# shield.net
KiCad netlist of a schematic drawn in EAGLE
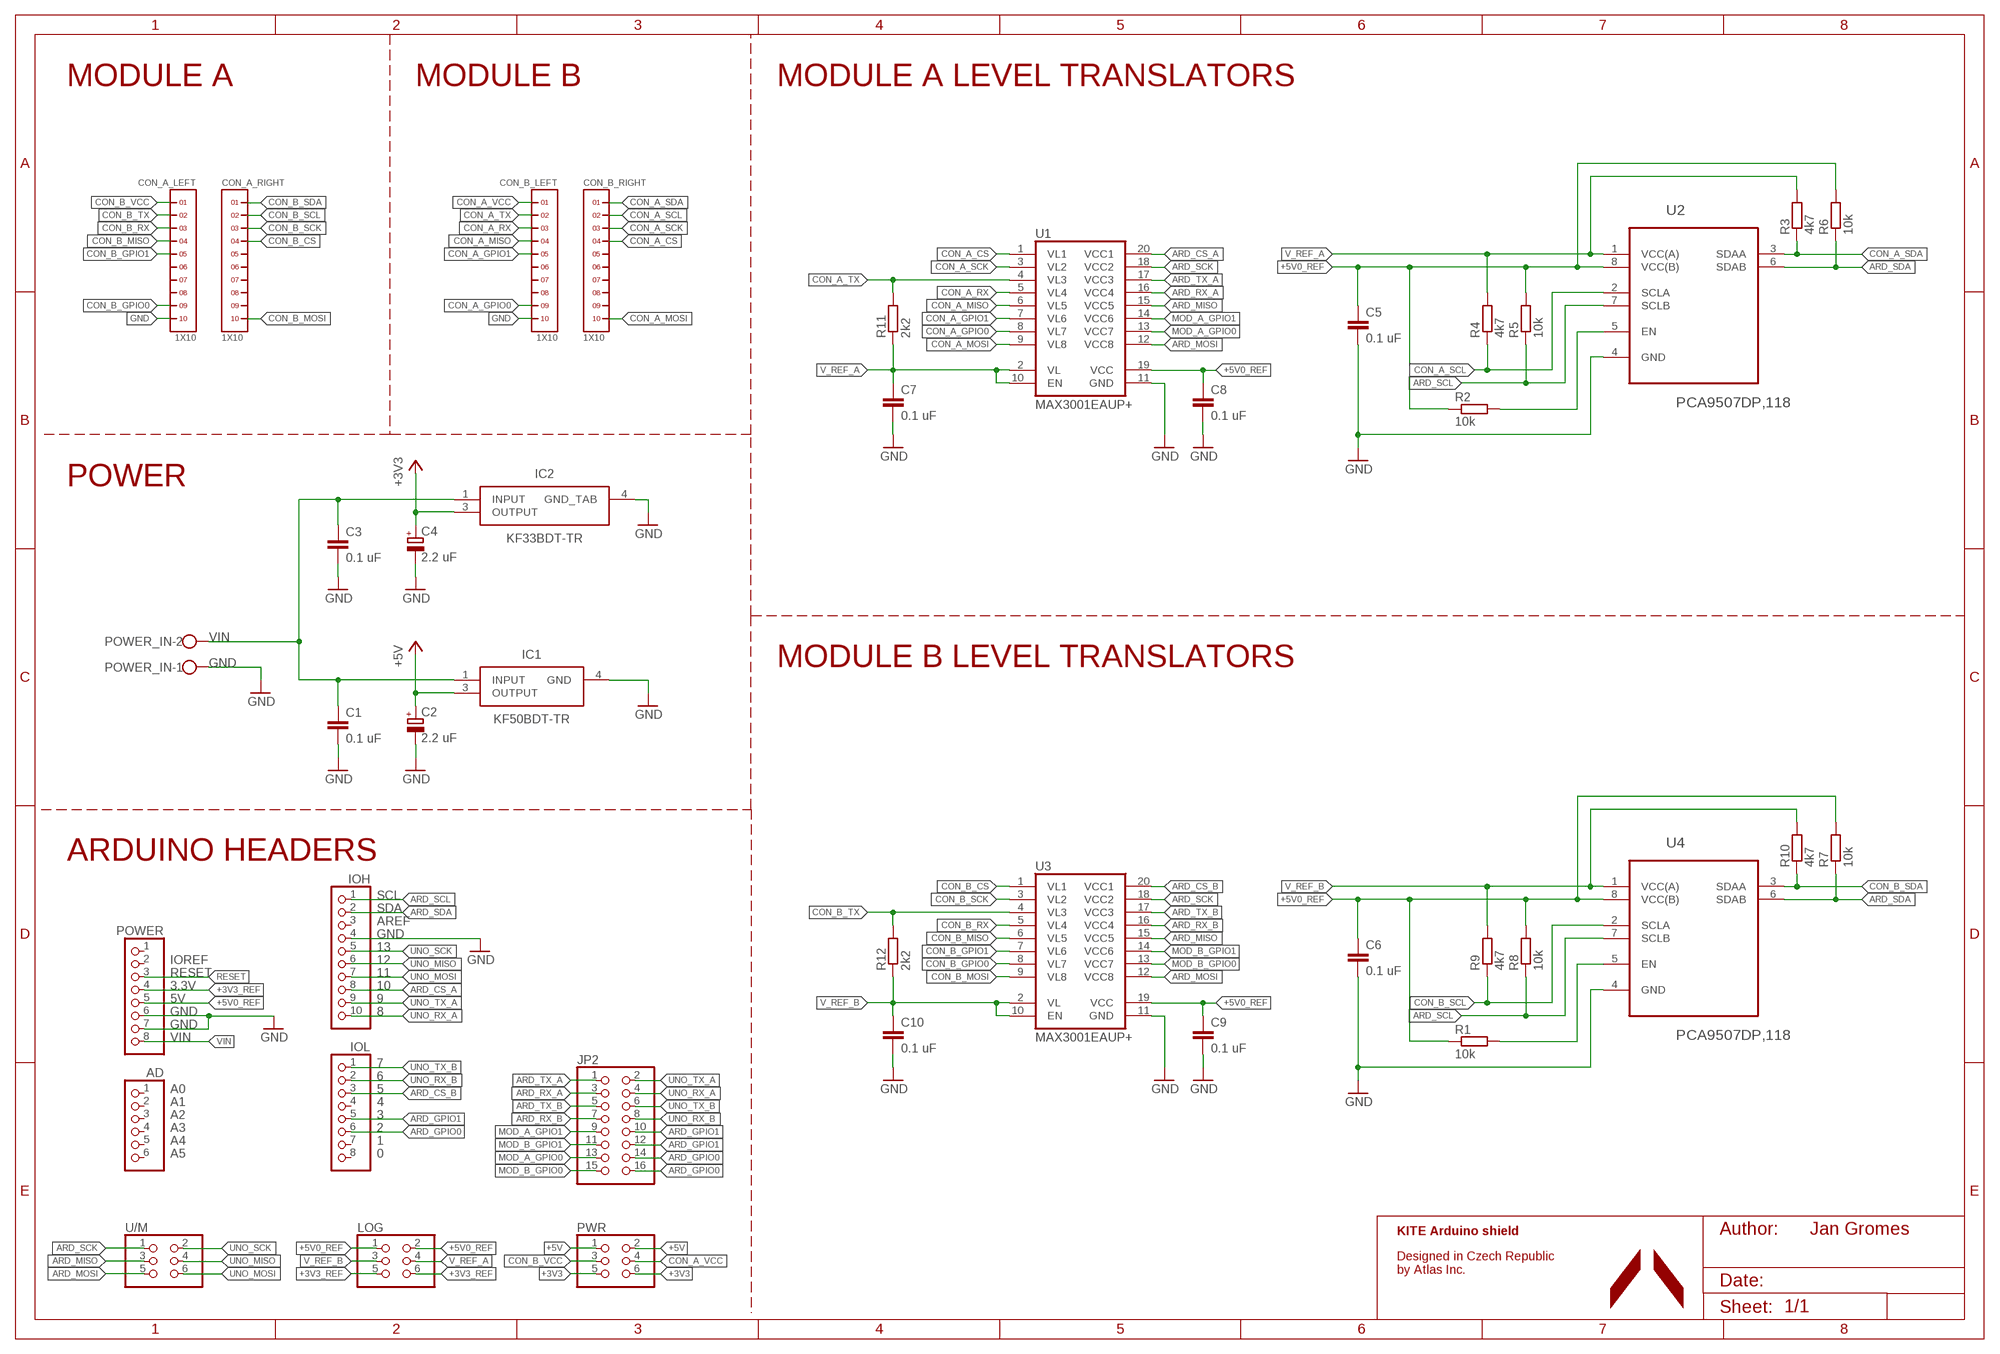
[diagram p0: schematic, sheet 1]

(export (version "E")
  (design (tool "Eeschema 10.0.6"))
  (components
    (comp (ref "AD")
      (value "PINHD-1X6")
      (footprint "eagle-import:1X06")
      (libsource (lib "eagle-import") (part "PINHD-1X6"))
    )
    (comp (ref "C1")
      (value "0.1 uF")
      (footprint "eagle-import:C0603")
      (libsource (lib "eagle-import") (part "C-EUC0603"))
    )
    (comp (ref "C2")
      (value "2.2 uF")
      (footprint "eagle-import:SMC_A")
      (libsource (lib "eagle-import") (part "CPOL-EUSMCA"))
    )
    (comp (ref "C3")
      (value "0.1 uF")
      (footprint "eagle-import:C0603")
      (libsource (lib "eagle-import") (part "C-EUC0603"))
    )
    (comp (ref "C4")
      (value "2.2 uF")
      (footprint "eagle-import:SMC_A")
      (libsource (lib "eagle-import") (part "CPOL-EUSMCA"))
    )
    (comp (ref "C5")
      (value "0.1 uF")
      (footprint "eagle-import:C0603")
      (libsource (lib "eagle-import") (part "C-EUC0603"))
    )
    (comp (ref "C6")
      (value "0.1 uF")
      (footprint "eagle-import:C0603")
      (libsource (lib "eagle-import") (part "C-EUC0603"))
    )
    (comp (ref "C7")
      (value "0.1 uF")
      (footprint "eagle-import:C0603")
      (libsource (lib "eagle-import") (part "C-EUC0603"))
    )
    (comp (ref "C8")
      (value "0.1 uF")
      (footprint "eagle-import:C0603")
      (libsource (lib "eagle-import") (part "C-EUC0603"))
    )
    (comp (ref "C9")
      (value "0.1 uF")
      (footprint "eagle-import:C0603")
      (libsource (lib "eagle-import") (part "C-EUC0603"))
    )
    (comp (ref "C10")
      (value "0.1 uF")
      (footprint "eagle-import:C0603")
      (libsource (lib "eagle-import") (part "C-EUC0603"))
    )
    (comp (ref "CON_A_LEFT")
      (value "1X10")
      (footprint "eagle-import:1X10")
      (libsource (lib "eagle-import") (part "1X10"))
    )
    (comp (ref "CON_A_RIGHT")
      (value "1X10")
      (footprint "eagle-import:1X10")
      (libsource (lib "eagle-import") (part "1X10"))
    )
    (comp (ref "CON_B_LEFT")
      (value "1X10")
      (footprint "eagle-import:1X10")
      (libsource (lib "eagle-import") (part "1X10"))
    )
    (comp (ref "CON_B_RIGHT")
      (value "1X10")
      (footprint "eagle-import:1X10")
      (libsource (lib "eagle-import") (part "1X10"))
    )
    (comp (ref "IC1")
      (value "KF50BDT-TR")
      (footprint "eagle-import:TO228P972X240-3N")
      (fields (field (name "RS_PART_NUMBER") "7140619"))
      (libsource (lib "eagle-import") (part "KF50BDT-TR"))
    )
    (comp (ref "IC2")
      (value "KF33BDT-TR")
      (footprint "eagle-import:TO228P972X240-3N")
      (fields (field (name "RS_PART_NUMBER") "7140616"))
      (libsource (lib "eagle-import") (part "KF33BDT-TR"))
    )
    (comp (ref "IOH")
      (value "PINHD-1X10")
      (footprint "eagle-import:1X10")
      (libsource (lib "eagle-import") (part "PINHD-1X10"))
    )
    (comp (ref "IOL")
      (value "PINHD-1X8")
      (footprint "eagle-import:1X08")
      (libsource (lib "eagle-import") (part "PINHD-1X8"))
    )
    (comp (ref "JP2")
      (value "PINHD-2X8")
      (footprint "eagle-import:2X08")
      (libsource (lib "eagle-import") (part "PINHD-2X8"))
    )
    (comp (ref "LOG")
      (value "PINHD-2X3")
      (footprint "eagle-import:2X03")
      (libsource (lib "eagle-import") (part "PINHD-2X3"))
    )
    (comp (ref "POWER")
      (value "PINHD-1X8")
      (footprint "eagle-import:1X08")
      (libsource (lib "eagle-import") (part "PINHD-1X8"))
    )
    (comp (ref "POWER_IN")
      (value "W237-102")
      (footprint "eagle-import:W237-102")
      (fields (field (name "MPN") "237-102"))
      (libsource (lib "eagle-import") (part "W237-102"))
    )
    (comp (ref "PWR")
      (value "PINHD-2X3")
      (footprint "eagle-import:2X03")
      (libsource (lib "eagle-import") (part "PINHD-2X3"))
    )
    (comp (ref "R1")
      (value "10k")
      (footprint "eagle-import:R0603")
      (libsource (lib "eagle-import") (part "R-EU_R0603"))
    )
    (comp (ref "R2")
      (value "10k")
      (footprint "eagle-import:R0603")
      (libsource (lib "eagle-import") (part "R-EU_R0603"))
    )
    (comp (ref "R3")
      (value "4k7")
      (footprint "eagle-import:R0603")
      (libsource (lib "eagle-import") (part "R-EU_R0603"))
    )
    (comp (ref "R4")
      (value "4k7")
      (footprint "eagle-import:R0603")
      (libsource (lib "eagle-import") (part "R-EU_R0603"))
    )
    (comp (ref "R5")
      (value "10k")
      (footprint "eagle-import:R0603")
      (libsource (lib "eagle-import") (part "R-EU_R0603"))
    )
    (comp (ref "R6")
      (value "10k")
      (footprint "eagle-import:R0603")
      (libsource (lib "eagle-import") (part "R-EU_R0603"))
    )
    (comp (ref "R7")
      (value "10k")
      (footprint "eagle-import:R0603")
      (libsource (lib "eagle-import") (part "R-EU_R0603"))
    )
    (comp (ref "R8")
      (value "10k")
      (footprint "eagle-import:R0603")
      (libsource (lib "eagle-import") (part "R-EU_R0603"))
    )
    (comp (ref "R9")
      (value "4k7")
      (footprint "eagle-import:R0603")
      (libsource (lib "eagle-import") (part "R-EU_R0603"))
    )
    (comp (ref "R10")
      (value "4k7")
      (footprint "eagle-import:R0603")
      (libsource (lib "eagle-import") (part "R-EU_R0603"))
    )
    (comp (ref "R11")
      (value "2k2")
      (footprint "eagle-import:R0603")
      (libsource (lib "eagle-import") (part "R-EU_R0603"))
    )
    (comp (ref "R12")
      (value "2k2")
      (footprint "eagle-import:R0603")
      (libsource (lib "eagle-import") (part "R-EU_R0603"))
    )
    (comp (ref "U/M")
      (value "PINHD-2X3")
      (footprint "eagle-import:2X03")
      (libsource (lib "eagle-import") (part "PINHD-2X3"))
    )
    (comp (ref "U1")
      (value "MAX3001EAUP+")
      (footprint "eagle-import:TSSOP20")
      (libsource (lib "eagle-import") (part "MAX3001"))
    )
    (comp (ref "U2")
      (value "PCA9507DP,118")
      (footprint "eagle-import:SOP65P490X110-8N")
      (libsource (lib "eagle-import") (part "PCA9507DP,118"))
    )
    (comp (ref "U3")
      (value "MAX3001EAUP+")
      (footprint "eagle-import:TSSOP20")
      (libsource (lib "eagle-import") (part "MAX3001"))
    )
    (comp (ref "U4")
      (value "PCA9507DP,118")
      (footprint "eagle-import:SOP65P490X110-8N")
      (libsource (lib "eagle-import") (part "PCA9507DP,118"))
    )
  )
  (nets
    (net (code "1") (name "+3V3") (class "Default")
      (node (ref "C4") (pin "+") (pinfunction "+_+") (pintype "passive"))
      (node (ref "IC2") (pin "3") (pinfunction "OUTPUT_3") (pintype "output"))
      (node (ref "PWR") (pin "5") (pinfunction "5_5") (pintype "passive"))
      (node (ref "PWR") (pin "6") (pinfunction "6_6") (pintype "passive"))
    )
    (net (code "2") (name "+3V3_REF") (class "Default")
      (node (ref "LOG") (pin "5") (pinfunction "5_5") (pintype "passive"))
      (node (ref "LOG") (pin "6") (pinfunction "6_6") (pintype "passive"))
      (node (ref "POWER") (pin "4") (pinfunction "4_4") (pintype "passive"))
    )
    (net (code "3") (name "+5V") (class "Default")
      (node (ref "C2") (pin "+") (pinfunction "+_+") (pintype "passive"))
      (node (ref "IC1") (pin "3") (pinfunction "OUTPUT_3") (pintype "power_in"))
      (node (ref "PWR") (pin "1") (pinfunction "1_1") (pintype "passive"))
      (node (ref "PWR") (pin "2") (pinfunction "2_2") (pintype "passive"))
    )
    (net (code "4") (name "+5V0_REF") (class "Default")
      (node (ref "C5") (pin "1") (pinfunction "1_1") (pintype "passive"))
      (node (ref "C6") (pin "1") (pinfunction "1_1") (pintype "passive"))
      (node (ref "C8") (pin "1") (pinfunction "1_1") (pintype "passive"))
      (node (ref "C9") (pin "1") (pinfunction "1_1") (pintype "passive"))
      (node (ref "LOG") (pin "1") (pinfunction "1_1") (pintype "passive"))
      (node (ref "LOG") (pin "2") (pinfunction "2_2") (pintype "passive"))
      (node (ref "POWER") (pin "5") (pinfunction "5_5") (pintype "passive"))
      (node (ref "R1") (pin "1") (pinfunction "1_1") (pintype "passive"))
      (node (ref "R2") (pin "1") (pinfunction "1_1") (pintype "passive"))
      (node (ref "R5") (pin "2") (pinfunction "2_2") (pintype "passive"))
      (node (ref "R6") (pin "2") (pinfunction "2_2") (pintype "passive"))
      (node (ref "R7") (pin "2") (pinfunction "2_2") (pintype "passive"))
      (node (ref "R8") (pin "2") (pinfunction "2_2") (pintype "passive"))
      (node (ref "U1") (pin "19") (pinfunction "VCC_19") (pintype "power_in"))
      (node (ref "U2") (pin "8") (pinfunction "VCC(B)_8") (pintype "power_in"))
      (node (ref "U3") (pin "19") (pinfunction "VCC_19") (pintype "power_in"))
      (node (ref "U4") (pin "8") (pinfunction "VCC(B)_8") (pintype "power_in"))
    )
    (net (code "5") (name "ARD_CS_A") (class "Default")
      (node (ref "IOH") (pin "8") (pinfunction "8_8") (pintype "passive"))
      (node (ref "U1") (pin "20") (pinfunction "VCC1_20") (pintype "bidirectional"))
    )
    (net (code "6") (name "ARD_CS_B") (class "Default")
      (node (ref "IOL") (pin "3") (pinfunction "3_3") (pintype "passive"))
      (node (ref "U3") (pin "20") (pinfunction "VCC1_20") (pintype "bidirectional"))
    )
    (net (code "7") (name "ARD_GPIO0") (class "Default")
      (node (ref "IOL") (pin "6") (pinfunction "6_6") (pintype "passive"))
      (node (ref "JP2") (pin "14") (pinfunction "14_14") (pintype "passive"))
      (node (ref "JP2") (pin "16") (pinfunction "16_16") (pintype "passive"))
    )
    (net (code "8") (name "ARD_GPIO1") (class "Default")
      (node (ref "IOL") (pin "5") (pinfunction "5_5") (pintype "passive"))
      (node (ref "JP2") (pin "10") (pinfunction "10_10") (pintype "passive"))
      (node (ref "JP2") (pin "12") (pinfunction "12_12") (pintype "passive"))
    )
    (net (code "9") (name "ARD_MISO") (class "Default")
      (node (ref "U/M") (pin "3") (pinfunction "3_3") (pintype "passive"))
      (node (ref "U1") (pin "15") (pinfunction "VCC5_15") (pintype "bidirectional"))
      (node (ref "U3") (pin "15") (pinfunction "VCC5_15") (pintype "bidirectional"))
    )
    (net (code "10") (name "ARD_MOSI") (class "Default")
      (node (ref "U/M") (pin "5") (pinfunction "5_5") (pintype "passive"))
      (node (ref "U1") (pin "12") (pinfunction "VCC8_12") (pintype "bidirectional"))
      (node (ref "U3") (pin "12") (pinfunction "VCC8_12") (pintype "bidirectional"))
    )
    (net (code "11") (name "ARD_RX_A") (class "Default")
      (node (ref "JP2") (pin "3") (pinfunction "3_3") (pintype "passive"))
      (node (ref "U1") (pin "16") (pinfunction "VCC4_16") (pintype "bidirectional"))
    )
    (net (code "12") (name "ARD_RX_B") (class "Default")
      (node (ref "JP2") (pin "7") (pinfunction "7_7") (pintype "passive"))
      (node (ref "U3") (pin "16") (pinfunction "VCC4_16") (pintype "bidirectional"))
    )
    (net (code "13") (name "ARD_SCK") (class "Default")
      (node (ref "U/M") (pin "1") (pinfunction "1_1") (pintype "passive"))
      (node (ref "U1") (pin "18") (pinfunction "VCC2_18") (pintype "bidirectional"))
      (node (ref "U3") (pin "18") (pinfunction "VCC2_18") (pintype "bidirectional"))
    )
    (net (code "14") (name "ARD_SCL") (class "Default")
      (node (ref "IOH") (pin "1") (pinfunction "1_1") (pintype "passive"))
      (node (ref "R5") (pin "1") (pinfunction "1_1") (pintype "passive"))
      (node (ref "R8") (pin "1") (pinfunction "1_1") (pintype "passive"))
      (node (ref "U2") (pin "7") (pinfunction "SCLB_7") (pintype "input"))
      (node (ref "U4") (pin "7") (pinfunction "SCLB_7") (pintype "input"))
    )
    (net (code "15") (name "ARD_SDA") (class "Default")
      (node (ref "IOH") (pin "2") (pinfunction "2_2") (pintype "passive"))
      (node (ref "R6") (pin "1") (pinfunction "1_1") (pintype "passive"))
      (node (ref "R7") (pin "1") (pinfunction "1_1") (pintype "passive"))
      (node (ref "U2") (pin "6") (pinfunction "SDAB_6") (pintype "bidirectional"))
      (node (ref "U4") (pin "6") (pinfunction "SDAB_6") (pintype "bidirectional"))
    )
    (net (code "16") (name "ARD_TX_A") (class "Default")
      (node (ref "JP2") (pin "1") (pinfunction "1_1") (pintype "passive"))
      (node (ref "U1") (pin "17") (pinfunction "VCC3_17") (pintype "bidirectional"))
    )
    (net (code "17") (name "ARD_TX_B") (class "Default")
      (node (ref "JP2") (pin "5") (pinfunction "5_5") (pintype "passive"))
      (node (ref "U3") (pin "17") (pinfunction "VCC3_17") (pintype "bidirectional"))
    )
    (net (code "18") (name "CON_A_CS") (class "Default")
      (node (ref "CON_B_RIGHT") (pin "4") (pinfunction "4_4") (pintype "bidirectional"))
      (node (ref "U1") (pin "1") (pinfunction "VL1_1") (pintype "bidirectional"))
    )
    (net (code "19") (name "CON_A_GPIO0") (class "Default")
      (node (ref "CON_B_LEFT") (pin "9") (pinfunction "9_9") (pintype "bidirectional"))
      (node (ref "U1") (pin "8") (pinfunction "VL7_8") (pintype "bidirectional"))
    )
    (net (code "20") (name "CON_A_GPIO1") (class "Default")
      (node (ref "CON_B_LEFT") (pin "5") (pinfunction "5_5") (pintype "bidirectional"))
      (node (ref "U1") (pin "7") (pinfunction "VL6_7") (pintype "bidirectional"))
    )
    (net (code "21") (name "CON_A_MISO") (class "Default")
      (node (ref "CON_B_LEFT") (pin "4") (pinfunction "4_4") (pintype "bidirectional"))
      (node (ref "U1") (pin "6") (pinfunction "VL5_6") (pintype "bidirectional"))
    )
    (net (code "22") (name "CON_A_MOSI") (class "Default")
      (node (ref "CON_B_RIGHT") (pin "10") (pinfunction "10_10") (pintype "bidirectional"))
      (node (ref "U1") (pin "9") (pinfunction "VL8_9") (pintype "bidirectional"))
    )
    (net (code "23") (name "CON_A_RX") (class "Default")
      (node (ref "CON_B_LEFT") (pin "3") (pinfunction "3_3") (pintype "bidirectional"))
      (node (ref "U1") (pin "5") (pinfunction "VL4_5") (pintype "bidirectional"))
    )
    (net (code "24") (name "CON_A_SCK") (class "Default")
      (node (ref "CON_B_RIGHT") (pin "3") (pinfunction "3_3") (pintype "bidirectional"))
      (node (ref "U1") (pin "3") (pinfunction "VL2_3") (pintype "bidirectional"))
    )
    (net (code "25") (name "CON_A_SCL") (class "Default")
      (node (ref "CON_B_RIGHT") (pin "2") (pinfunction "2_2") (pintype "bidirectional"))
      (node (ref "R4") (pin "1") (pinfunction "1_1") (pintype "passive"))
      (node (ref "U2") (pin "2") (pinfunction "SCLA_2") (pintype "input"))
    )
    (net (code "26") (name "CON_A_SDA") (class "Default")
      (node (ref "CON_B_RIGHT") (pin "1") (pinfunction "1_1") (pintype "bidirectional"))
      (node (ref "R3") (pin "1") (pinfunction "1_1") (pintype "passive"))
      (node (ref "U2") (pin "3") (pinfunction "SDAA_3") (pintype "bidirectional"))
    )
    (net (code "27") (name "CON_A_TX") (class "Default")
      (node (ref "CON_B_LEFT") (pin "2") (pinfunction "2_2") (pintype "bidirectional"))
      (node (ref "R11") (pin "2") (pinfunction "2_2") (pintype "passive"))
      (node (ref "U1") (pin "4") (pinfunction "VL3_4") (pintype "bidirectional"))
    )
    (net (code "28") (name "CON_A_VCC") (class "Default")
      (node (ref "CON_B_LEFT") (pin "1") (pinfunction "1_1") (pintype "bidirectional"))
      (node (ref "PWR") (pin "4") (pinfunction "4_4") (pintype "passive"))
    )
    (net (code "29") (name "CON_B_CS") (class "Default")
      (node (ref "CON_A_RIGHT") (pin "4") (pinfunction "4_4") (pintype "bidirectional"))
      (node (ref "U3") (pin "1") (pinfunction "VL1_1") (pintype "bidirectional"))
    )
    (net (code "30") (name "CON_B_GPIO0") (class "Default")
      (node (ref "CON_A_LEFT") (pin "9") (pinfunction "9_9") (pintype "bidirectional"))
      (node (ref "U3") (pin "8") (pinfunction "VL7_8") (pintype "bidirectional"))
    )
    (net (code "31") (name "CON_B_GPIO1") (class "Default")
      (node (ref "CON_A_LEFT") (pin "5") (pinfunction "5_5") (pintype "bidirectional"))
      (node (ref "U3") (pin "7") (pinfunction "VL6_7") (pintype "bidirectional"))
    )
    (net (code "32") (name "CON_B_MISO") (class "Default")
      (node (ref "CON_A_LEFT") (pin "4") (pinfunction "4_4") (pintype "bidirectional"))
      (node (ref "U3") (pin "6") (pinfunction "VL5_6") (pintype "bidirectional"))
    )
    (net (code "33") (name "CON_B_MOSI") (class "Default")
      (node (ref "CON_A_RIGHT") (pin "10") (pinfunction "10_10") (pintype "bidirectional"))
      (node (ref "U3") (pin "9") (pinfunction "VL8_9") (pintype "bidirectional"))
    )
    (net (code "34") (name "CON_B_RX") (class "Default")
      (node (ref "CON_A_LEFT") (pin "3") (pinfunction "3_3") (pintype "bidirectional"))
      (node (ref "U3") (pin "5") (pinfunction "VL4_5") (pintype "bidirectional"))
    )
    (net (code "35") (name "CON_B_SCK") (class "Default")
      (node (ref "CON_A_RIGHT") (pin "3") (pinfunction "3_3") (pintype "bidirectional"))
      (node (ref "U3") (pin "3") (pinfunction "VL2_3") (pintype "bidirectional"))
    )
    (net (code "36") (name "CON_B_SCL") (class "Default")
      (node (ref "CON_A_RIGHT") (pin "2") (pinfunction "2_2") (pintype "bidirectional"))
      (node (ref "R9") (pin "1") (pinfunction "1_1") (pintype "passive"))
      (node (ref "U4") (pin "2") (pinfunction "SCLA_2") (pintype "input"))
    )
    (net (code "37") (name "CON_B_SDA") (class "Default")
      (node (ref "CON_A_RIGHT") (pin "1") (pinfunction "1_1") (pintype "bidirectional"))
      (node (ref "R10") (pin "1") (pinfunction "1_1") (pintype "passive"))
      (node (ref "U4") (pin "3") (pinfunction "SDAA_3") (pintype "bidirectional"))
    )
    (net (code "38") (name "CON_B_TX") (class "Default")
      (node (ref "CON_A_LEFT") (pin "2") (pinfunction "2_2") (pintype "bidirectional"))
      (node (ref "R12") (pin "2") (pinfunction "2_2") (pintype "passive"))
      (node (ref "U3") (pin "4") (pinfunction "VL3_4") (pintype "bidirectional"))
    )
    (net (code "39") (name "CON_B_VCC") (class "Default")
      (node (ref "CON_A_LEFT") (pin "1") (pinfunction "1_1") (pintype "bidirectional"))
      (node (ref "PWR") (pin "3") (pinfunction "3_3") (pintype "passive"))
    )
    (net (code "40") (name "GND") (class "Default")
      (node (ref "C1") (pin "2") (pinfunction "2_2") (pintype "passive"))
      (node (ref "C10") (pin "2") (pinfunction "2_2") (pintype "passive"))
      (node (ref "C2") (pin "-") (pinfunction "-_-") (pintype "passive"))
      (node (ref "C3") (pin "2") (pinfunction "2_2") (pintype "passive"))
      (node (ref "C4") (pin "-") (pinfunction "-_-") (pintype "passive"))
      (node (ref "C5") (pin "2") (pinfunction "2_2") (pintype "passive"))
      (node (ref "C6") (pin "2") (pinfunction "2_2") (pintype "passive"))
      (node (ref "C7") (pin "2") (pinfunction "2_2") (pintype "passive"))
      (node (ref "C8") (pin "2") (pinfunction "2_2") (pintype "passive"))
      (node (ref "C9") (pin "2") (pinfunction "2_2") (pintype "passive"))
      (node (ref "CON_A_LEFT") (pin "10") (pinfunction "10_10") (pintype "bidirectional"))
      (node (ref "CON_B_LEFT") (pin "10") (pinfunction "10_10") (pintype "bidirectional"))
      (node (ref "IC1") (pin "4") (pinfunction "GND_4") (pintype "input"))
      (node (ref "IC2") (pin "4") (pinfunction "GND_TAB_4") (pintype "power_in"))
      (node (ref "IOH") (pin "4") (pinfunction "4_4") (pintype "passive"))
      (node (ref "POWER") (pin "6") (pinfunction "6_6") (pintype "passive"))
      (node (ref "POWER") (pin "7") (pinfunction "7_7") (pintype "passive"))
      (node (ref "POWER_IN") (pin "1") (pinfunction "KL_1") (pintype "passive"))
      (node (ref "U1") (pin "11") (pinfunction "GND_11") (pintype "power_in"))
      (node (ref "U2") (pin "4") (pinfunction "GND_4") (pintype "passive"))
      (node (ref "U3") (pin "11") (pinfunction "GND_11") (pintype "power_in"))
      (node (ref "U4") (pin "4") (pinfunction "GND_4") (pintype "passive"))
    )
    (net (code "41") (name "MOD_A_GPIO0") (class "Default")
      (node (ref "JP2") (pin "13") (pinfunction "13_13") (pintype "passive"))
      (node (ref "U1") (pin "13") (pinfunction "VCC7_13") (pintype "bidirectional"))
    )
    (net (code "42") (name "MOD_A_GPIO1") (class "Default")
      (node (ref "JP2") (pin "9") (pinfunction "9_9") (pintype "passive"))
      (node (ref "U1") (pin "14") (pinfunction "VCC6_14") (pintype "bidirectional"))
    )
    (net (code "43") (name "MOD_B_GPIO0") (class "Default")
      (node (ref "JP2") (pin "15") (pinfunction "15_15") (pintype "passive"))
      (node (ref "U3") (pin "13") (pinfunction "VCC7_13") (pintype "bidirectional"))
    )
    (net (code "44") (name "MOD_B_GPIO1") (class "Default")
      (node (ref "JP2") (pin "11") (pinfunction "11_11") (pintype "passive"))
      (node (ref "U3") (pin "14") (pinfunction "VCC6_14") (pintype "bidirectional"))
    )
    (net (code "45") (name "Net-(U2-EN)") (class "Default")
      (node (ref "R2") (pin "2") (pinfunction "2_2") (pintype "passive"))
      (node (ref "U2") (pin "5") (pinfunction "EN_5") (pintype "input"))
    )
    (net (code "46") (name "Net-(U4-EN)") (class "Default")
      (node (ref "R1") (pin "2") (pinfunction "2_2") (pintype "passive"))
      (node (ref "U4") (pin "5") (pinfunction "EN_5") (pintype "input"))
    )
    (net (code "47") (name "RESET") (class "Default")
      (node (ref "POWER") (pin "3") (pinfunction "3_3") (pintype "passive"))
    )
    (net (code "48") (name "UNO_MISO") (class "Default")
      (node (ref "IOH") (pin "6") (pinfunction "6_6") (pintype "passive"))
      (node (ref "U/M") (pin "4") (pinfunction "4_4") (pintype "passive"))
    )
    (net (code "49") (name "UNO_MOSI") (class "Default")
      (node (ref "IOH") (pin "7") (pinfunction "7_7") (pintype "passive"))
      (node (ref "U/M") (pin "6") (pinfunction "6_6") (pintype "passive"))
    )
    (net (code "50") (name "UNO_RX_A") (class "Default")
      (node (ref "IOH") (pin "10") (pinfunction "10_10") (pintype "passive"))
      (node (ref "JP2") (pin "4") (pinfunction "4_4") (pintype "passive"))
    )
    (net (code "51") (name "UNO_RX_B") (class "Default")
      (node (ref "IOL") (pin "2") (pinfunction "2_2") (pintype "passive"))
      (node (ref "JP2") (pin "8") (pinfunction "8_8") (pintype "passive"))
    )
    (net (code "52") (name "UNO_SCK") (class "Default")
      (node (ref "IOH") (pin "5") (pinfunction "5_5") (pintype "passive"))
      (node (ref "U/M") (pin "2") (pinfunction "2_2") (pintype "passive"))
    )
    (net (code "53") (name "UNO_TX_A") (class "Default")
      (node (ref "IOH") (pin "9") (pinfunction "9_9") (pintype "passive"))
      (node (ref "JP2") (pin "2") (pinfunction "2_2") (pintype "passive"))
    )
    (net (code "54") (name "UNO_TX_B") (class "Default")
      (node (ref "IOL") (pin "1") (pinfunction "1_1") (pintype "passive"))
      (node (ref "JP2") (pin "6") (pinfunction "6_6") (pintype "passive"))
    )
    (net (code "55") (name "VIN") (class "Default")
      (node (ref "C1") (pin "1") (pinfunction "1_1") (pintype "passive"))
      (node (ref "C3") (pin "1") (pinfunction "1_1") (pintype "passive"))
      (node (ref "IC1") (pin "1") (pinfunction "INPUT_1") (pintype "output"))
      (node (ref "IC2") (pin "1") (pinfunction "INPUT_1") (pintype "input"))
      (node (ref "POWER") (pin "8") (pinfunction "8_8") (pintype "passive"))
      (node (ref "POWER_IN") (pin "2") (pinfunction "KL_2") (pintype "passive"))
    )
    (net (code "56") (name "V_REF_A") (class "Default")
      (node (ref "C7") (pin "1") (pinfunction "1_1") (pintype "passive"))
      (node (ref "LOG") (pin "4") (pinfunction "4_4") (pintype "passive"))
      (node (ref "R11") (pin "1") (pinfunction "1_1") (pintype "passive"))
      (node (ref "R3") (pin "2") (pinfunction "2_2") (pintype "passive"))
      (node (ref "R4") (pin "2") (pinfunction "2_2") (pintype "passive"))
      (node (ref "U1") (pin "10") (pinfunction "EN_10") (pintype "power_in"))
      (node (ref "U1") (pin "2") (pinfunction "VL_2") (pintype "input"))
      (node (ref "U2") (pin "1") (pinfunction "VCC(A)_1") (pintype "power_in"))
    )
    (net (code "57") (name "V_REF_B") (class "Default")
      (node (ref "C10") (pin "1") (pinfunction "1_1") (pintype "passive"))
      (node (ref "LOG") (pin "3") (pinfunction "3_3") (pintype "passive"))
      (node (ref "R10") (pin "2") (pinfunction "2_2") (pintype "passive"))
      (node (ref "R12") (pin "1") (pinfunction "1_1") (pintype "passive"))
      (node (ref "R9") (pin "2") (pinfunction "2_2") (pintype "passive"))
      (node (ref "U3") (pin "10") (pinfunction "EN_10") (pintype "power_in"))
      (node (ref "U3") (pin "2") (pinfunction "VL_2") (pintype "input"))
      (node (ref "U4") (pin "1") (pinfunction "VCC(A)_1") (pintype "power_in"))
    )
    (net (code "58") (name "unconnected-(AD-Pad1)") (class "Default")
      (node (ref "AD") (pin "1") (pinfunction "1_1") (pintype "passive"))
    )
    (net (code "59") (name "unconnected-(AD-Pad2)") (class "Default")
      (node (ref "AD") (pin "2") (pinfunction "2_2") (pintype "passive"))
    )
    (net (code "60") (name "unconnected-(AD-Pad3)") (class "Default")
      (node (ref "AD") (pin "3") (pinfunction "3_3") (pintype "passive"))
    )
    (net (code "61") (name "unconnected-(AD-Pad4)") (class "Default")
      (node (ref "AD") (pin "4") (pinfunction "4_4") (pintype "passive"))
    )
    (net (code "62") (name "unconnected-(AD-Pad5)") (class "Default")
      (node (ref "AD") (pin "5") (pinfunction "5_5") (pintype "passive"))
    )
    (net (code "63") (name "unconnected-(AD-Pad6)") (class "Default")
      (node (ref "AD") (pin "6") (pinfunction "6_6") (pintype "passive"))
    )
    (net (code "64") (name "unconnected-(CON_A_LEFT-Pad6)") (class "Default")
      (node (ref "CON_A_LEFT") (pin "6") (pinfunction "6_6") (pintype "bidirectional"))
    )
    (net (code "65") (name "unconnected-(CON_A_LEFT-Pad7)") (class "Default")
      (node (ref "CON_A_LEFT") (pin "7") (pinfunction "7_7") (pintype "bidirectional"))
    )
    (net (code "66") (name "unconnected-(CON_A_LEFT-Pad8)") (class "Default")
      (node (ref "CON_A_LEFT") (pin "8") (pinfunction "8_8") (pintype "bidirectional"))
    )
    (net (code "67") (name "unconnected-(CON_A_RIGHT-Pad5)") (class "Default")
      (node (ref "CON_A_RIGHT") (pin "5") (pinfunction "5_5") (pintype "bidirectional"))
    )
    (net (code "68") (name "unconnected-(CON_A_RIGHT-Pad6)") (class "Default")
      (node (ref "CON_A_RIGHT") (pin "6") (pinfunction "6_6") (pintype "bidirectional"))
    )
    (net (code "69") (name "unconnected-(CON_A_RIGHT-Pad7)") (class "Default")
      (node (ref "CON_A_RIGHT") (pin "7") (pinfunction "7_7") (pintype "bidirectional"))
    )
    (net (code "70") (name "unconnected-(CON_A_RIGHT-Pad8)") (class "Default")
      (node (ref "CON_A_RIGHT") (pin "8") (pinfunction "8_8") (pintype "bidirectional"))
    )
    (net (code "71") (name "unconnected-(CON_A_RIGHT-Pad9)") (class "Default")
      (node (ref "CON_A_RIGHT") (pin "9") (pinfunction "9_9") (pintype "bidirectional"))
    )
    (net (code "72") (name "unconnected-(CON_B_LEFT-Pad6)") (class "Default")
      (node (ref "CON_B_LEFT") (pin "6") (pinfunction "6_6") (pintype "bidirectional"))
    )
    (net (code "73") (name "unconnected-(CON_B_LEFT-Pad7)") (class "Default")
      (node (ref "CON_B_LEFT") (pin "7") (pinfunction "7_7") (pintype "bidirectional"))
    )
    (net (code "74") (name "unconnected-(CON_B_LEFT-Pad8)") (class "Default")
      (node (ref "CON_B_LEFT") (pin "8") (pinfunction "8_8") (pintype "bidirectional"))
    )
    (net (code "75") (name "unconnected-(CON_B_RIGHT-Pad5)") (class "Default")
      (node (ref "CON_B_RIGHT") (pin "5") (pinfunction "5_5") (pintype "bidirectional"))
    )
    (net (code "76") (name "unconnected-(CON_B_RIGHT-Pad6)") (class "Default")
      (node (ref "CON_B_RIGHT") (pin "6") (pinfunction "6_6") (pintype "bidirectional"))
    )
    (net (code "77") (name "unconnected-(CON_B_RIGHT-Pad7)") (class "Default")
      (node (ref "CON_B_RIGHT") (pin "7") (pinfunction "7_7") (pintype "bidirectional"))
    )
    (net (code "78") (name "unconnected-(CON_B_RIGHT-Pad8)") (class "Default")
      (node (ref "CON_B_RIGHT") (pin "8") (pinfunction "8_8") (pintype "bidirectional"))
    )
    (net (code "79") (name "unconnected-(CON_B_RIGHT-Pad9)") (class "Default")
      (node (ref "CON_B_RIGHT") (pin "9") (pinfunction "9_9") (pintype "bidirectional"))
    )
    (net (code "80") (name "unconnected-(IOH-Pad3)") (class "Default")
      (node (ref "IOH") (pin "3") (pinfunction "3_3") (pintype "passive"))
    )
    (net (code "81") (name "unconnected-(IOL-Pad4)") (class "Default")
      (node (ref "IOL") (pin "4") (pinfunction "4_4") (pintype "passive"))
    )
    (net (code "82") (name "unconnected-(IOL-Pad7)") (class "Default")
      (node (ref "IOL") (pin "7") (pinfunction "7_7") (pintype "passive"))
    )
    (net (code "83") (name "unconnected-(IOL-Pad8)") (class "Default")
      (node (ref "IOL") (pin "8") (pinfunction "8_8") (pintype "passive"))
    )
    (net (code "84") (name "unconnected-(POWER-Pad1)") (class "Default")
      (node (ref "POWER") (pin "1") (pinfunction "1_1") (pintype "passive"))
    )
    (net (code "85") (name "unconnected-(POWER-Pad2)") (class "Default")
      (node (ref "POWER") (pin "2") (pinfunction "2_2") (pintype "passive"))
    )
  )
)
